# DEBUG.net
KiCad netlist of a schematic drawn in Altium Designer
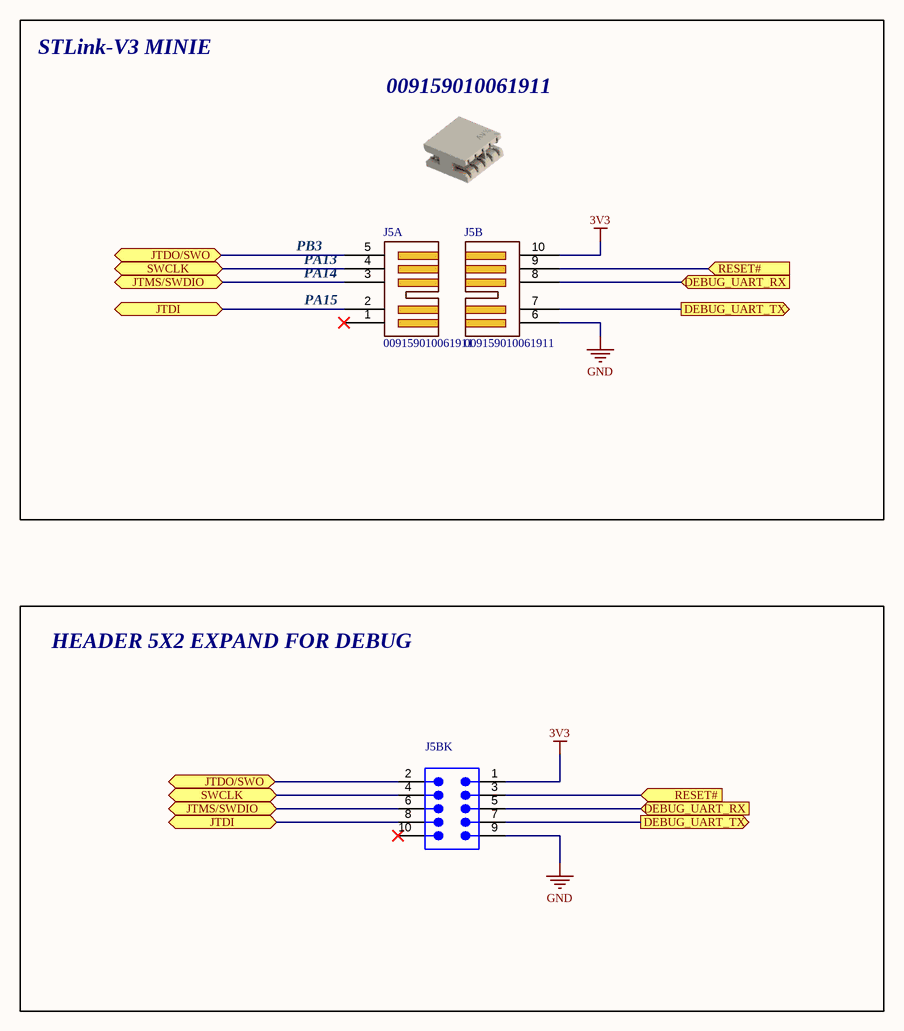
[diagram p0: DEBUG.SchDoc]

(export (version "E")
  (design (tool "Eeschema 10.0.6"))
  (components
    (comp (ref "J5")
      (value "009159010061911")
      (footprint "009159010061911")
      (description "pads for STLink V3 minie")
      (libsource (lib "") (part "009159010061911_1"))
    )
    (comp (ref "J5BK")
      (value "61301021121")
      (footprint "61301021121")
      (description "WR-PHD Pin Header, THT, Vertical, pitch 2.54mm, 2 Row, 10P")
      (fields (field (name "MANUFACTURER") "Wurth Elektronik"))
      (libsource (lib "COMM_SCHLIB") (part "61301021121"))
    )
  )
  (nets
    (net (code "1") (name "/DEBUG_UART_RX") (class "Default")
      (node (ref "J5") (pin "8") (pinfunction "8_8") (pintype "passive"))
      (node (ref "J5BK") (pin "5") (pinfunction "5_5") (pintype "passive"))
    )
    (net (code "2") (name "/DEBUG_UART_TX") (class "Default")
      (node (ref "J5") (pin "7") (pinfunction "7_7") (pintype "passive"))
      (node (ref "J5BK") (pin "7") (pinfunction "7_7") (pintype "passive"))
    )
    (net (code "3") (name "/JTDI") (class "Default")
      (node (ref "J5") (pin "2") (pintype "passive"))
      (node (ref "J5BK") (pin "8") (pinfunction "8_8") (pintype "passive"))
    )
    (net (code "4") (name "/JTDO{slash}SWO") (class "Default")
      (node (ref "J5") (pin "5") (pinfunction "5_5") (pintype "passive"))
      (node (ref "J5BK") (pin "2") (pinfunction "2_2") (pintype "passive"))
    )
    (net (code "5") (name "/JTMS{slash}SWDIO") (class "Default")
      (node (ref "J5") (pin "3") (pintype "passive"))
      (node (ref "J5BK") (pin "6") (pinfunction "6_6") (pintype "passive"))
    )
    (net (code "6") (name "/RESET#") (class "Default")
      (node (ref "J5") (pin "9") (pinfunction "9_9") (pintype "passive"))
      (node (ref "J5BK") (pin "3") (pinfunction "3_3") (pintype "passive"))
    )
    (net (code "7") (name "/SWCLK") (class "Default")
      (node (ref "J5") (pin "4") (pintype "passive"))
      (node (ref "J5BK") (pin "4") (pinfunction "4_4") (pintype "passive"))
    )
    (net (code "8") (name "3V3") (class "Default")
      (node (ref "J5") (pin "10") (pinfunction "10_10") (pintype "passive"))
      (node (ref "J5BK") (pin "1") (pinfunction "1_1") (pintype "passive"))
    )
    (net (code "9") (name "GND") (class "Default")
      (node (ref "J5") (pin "6") (pinfunction "6_6") (pintype "passive"))
      (node (ref "J5BK") (pin "9") (pinfunction "9_9") (pintype "passive"))
    )
    (net (code "10") (name "unconnected-(J5-Pad1)") (class "Default")
      (node (ref "J5") (pin "1") (pintype "passive+no_connect"))
    )
    (net (code "11") (name "unconnected-(J5BK-Pad10)") (class "Default")
      (node (ref "J5BK") (pin "10") (pinfunction "10_10") (pintype "passive+no_connect"))
    )
  )
)
